# breakout.net
KiCad netlist of a schematic drawn in EAGLE
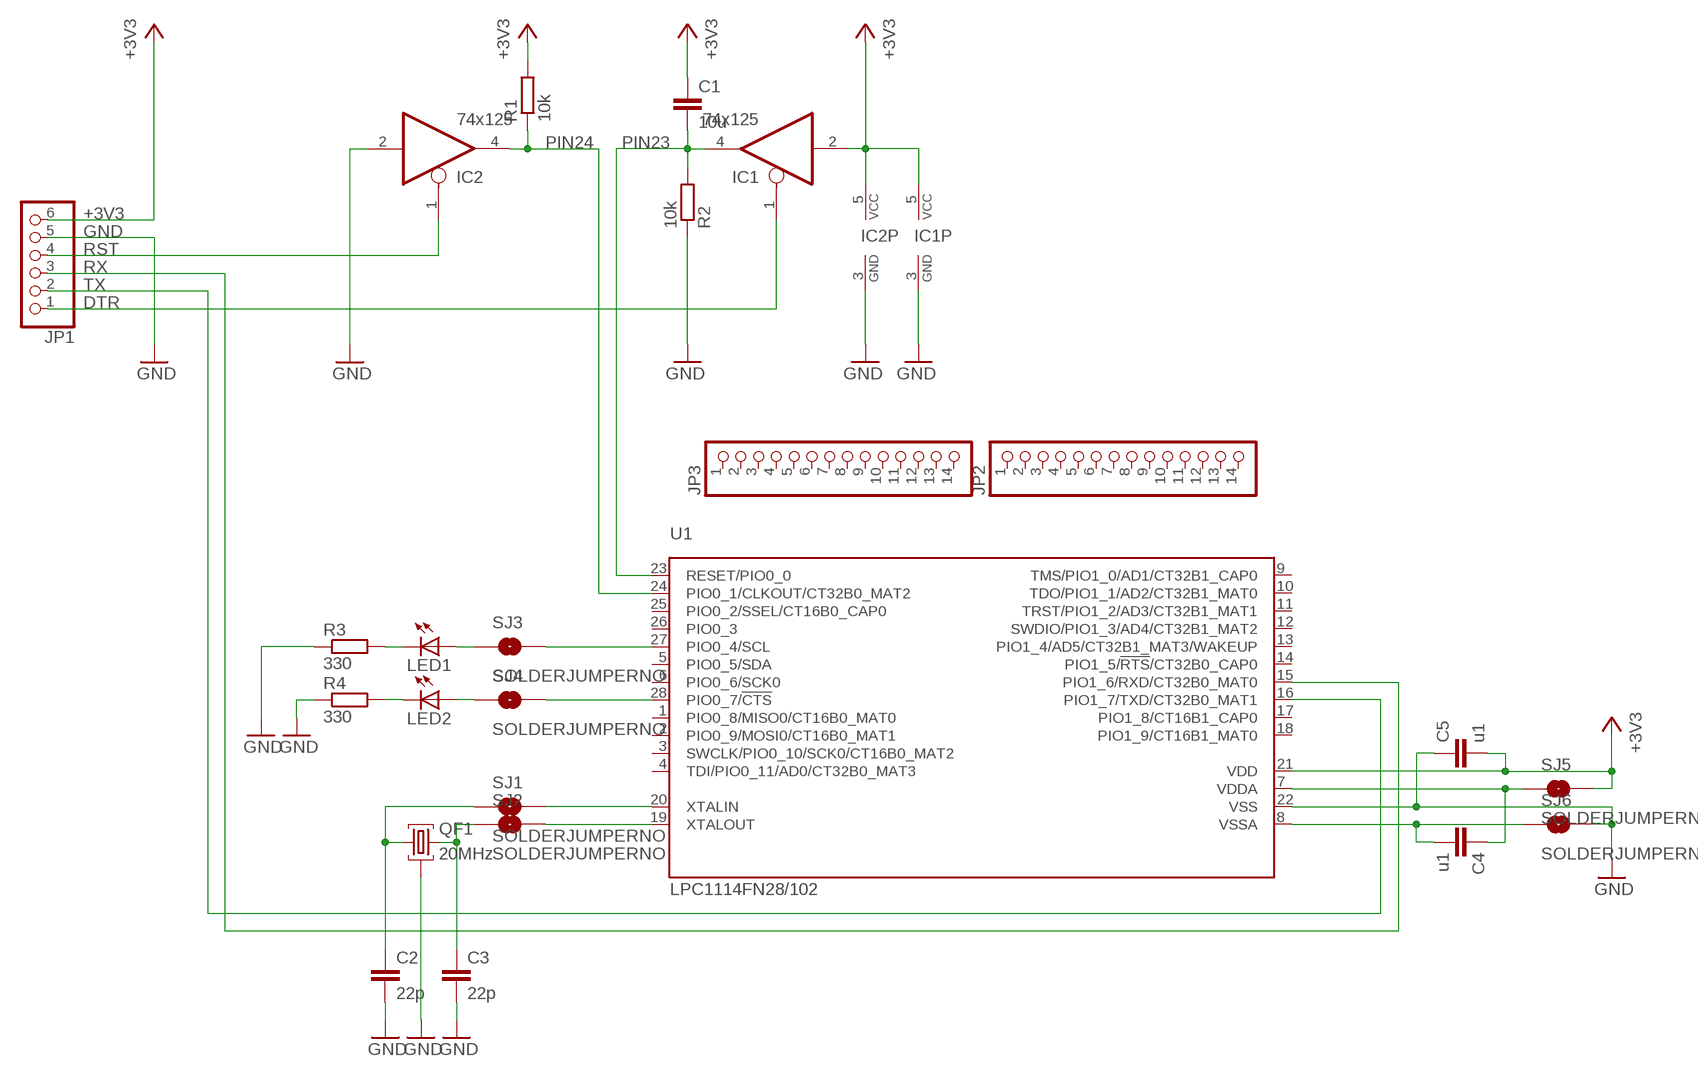
[diagram p0: schematic, sheet 1]

(export (version "E")
  (design (tool "Eeschema 10.0.6"))
  (components
    (comp (ref "C1")
      (value "10u")
      (footprint "eagle-import:C0805K")
      (libsource (lib "eagle-import") (part "C-EUC0805K"))
    )
    (comp (ref "C2")
      (value "22p")
      (footprint "eagle-import:C0805K")
      (libsource (lib "eagle-import") (part "C-EUC0805K"))
    )
    (comp (ref "C3")
      (value "22p")
      (footprint "eagle-import:C0805K")
      (libsource (lib "eagle-import") (part "C-EUC0805K"))
    )
    (comp (ref "C4")
      (value "u1")
      (footprint "eagle-import:C0805K")
      (libsource (lib "eagle-import") (part "C-EUC0805K"))
    )
    (comp (ref "C5")
      (value "u1")
      (footprint "eagle-import:C0805K")
      (libsource (lib "eagle-import") (part "C-EUC0805K"))
    )
    (comp (ref "IC1")
      (value "74x125")
      (footprint "eagle-import:SOT23-5")
      (libsource (lib "eagle-import") (part "741G125DBVAHC"))
    )
    (comp (ref "IC2")
      (value "74x125")
      (footprint "eagle-import:SOT23-5")
      (libsource (lib "eagle-import") (part "741G125DBVAHC"))
    )
    (comp (ref "JP1")
      (value "PINHD-1X6/90")
      (footprint "eagle-import:1X06_90")
      (libsource (lib "eagle-import") (part "PINHD-1X6/90"))
    )
    (comp (ref "JP2")
      (value "PINHD-1X14")
      (footprint "eagle-import:1X14")
      (libsource (lib "eagle-import") (part "PINHD-1X14"))
    )
    (comp (ref "JP3")
      (value "PINHD-1X14")
      (footprint "eagle-import:1X14")
      (libsource (lib "eagle-import") (part "PINHD-1X14"))
    )
    (comp (ref "LED1")
      (value "LEDLD260")
      (footprint "eagle-import:LD260")
      (libsource (lib "eagle-import") (part "LEDLD260"))
    )
    (comp (ref "LED2")
      (value "LEDLD260")
      (footprint "eagle-import:LD260")
      (libsource (lib "eagle-import") (part "LEDLD260"))
    )
    (comp (ref "QF1")
      (value "20MHz")
      (footprint "eagle-import:HC49U")
      (libsource (lib "eagle-import") (part "10MAHC49T7"))
    )
    (comp (ref "R1")
      (value "10k")
      (footprint "eagle-import:M0805")
      (libsource (lib "eagle-import") (part "R-EU_M0805"))
    )
    (comp (ref "R2")
      (value "10k")
      (footprint "eagle-import:M0805")
      (libsource (lib "eagle-import") (part "R-EU_M0805"))
    )
    (comp (ref "R3")
      (value "330")
      (footprint "eagle-import:M0805")
      (libsource (lib "eagle-import") (part "R-EU_M0805"))
    )
    (comp (ref "R4")
      (value "330")
      (footprint "eagle-import:M0805")
      (libsource (lib "eagle-import") (part "R-EU_M0805"))
    )
    (comp (ref "SJ1")
      (value "SOLDERJUMPERNO")
      (footprint "eagle-import:SJ_2S-NO")
      (libsource (lib "eagle-import") (part "SOLDERJUMPERNO"))
    )
    (comp (ref "SJ2")
      (value "SOLDERJUMPERNO")
      (footprint "eagle-import:SJ_2S-NO")
      (libsource (lib "eagle-import") (part "SOLDERJUMPERNO"))
    )
    (comp (ref "SJ3")
      (value "SOLDERJUMPERNO")
      (footprint "eagle-import:SJ_2S-NO")
      (libsource (lib "eagle-import") (part "SOLDERJUMPERNO"))
    )
    (comp (ref "SJ4")
      (value "SOLDERJUMPERNO")
      (footprint "eagle-import:SJ_2S-NO")
      (libsource (lib "eagle-import") (part "SOLDERJUMPERNO"))
    )
    (comp (ref "SJ5")
      (value "SOLDERJUMPERNO")
      (footprint "eagle-import:SJ_2S-NO")
      (libsource (lib "eagle-import") (part "SOLDERJUMPERNO"))
    )
    (comp (ref "SJ6")
      (value "SOLDERJUMPERNO")
      (footprint "eagle-import:SJ_2S-NO")
      (libsource (lib "eagle-import") (part "SOLDERJUMPERNO"))
    )
    (comp (ref "U1")
      (value "LPC1114FN28/102")
      (footprint "eagle-import:SOT117")
      (libsource (lib "eagle-import") (part "LPC1114FN28/102"))
    )
  )
  (nets
    (net (code "1") (name "+3V3") (class "Default")
      (node (ref "C1") (pin "1") (pinfunction "1_1") (pintype "passive"))
      (node (ref "C5") (pin "2") (pinfunction "2_2") (pintype "passive"))
      (node (ref "IC1") (pin "2") (pinfunction "I_2") (pintype "input"))
      (node (ref "IC1") (pin "5") (pinfunction "VCC_5") (pintype "power_in"))
      (node (ref "IC2") (pin "5") (pinfunction "VCC_5") (pintype "power_in"))
      (node (ref "JP1") (pin "6") (pinfunction "6_6") (pintype "passive"))
      (node (ref "R1") (pin "2") (pinfunction "2_2") (pintype "passive"))
      (node (ref "SJ5") (pin "2") (pinfunction "2_2") (pintype "passive"))
      (node (ref "U1") (pin "21") (pinfunction "VDD_21") (pintype "power_in"))
    )
    (net (code "2") (name "/DTR") (class "Default")
      (node (ref "IC1") (pin "1") (pinfunction "OE_1") (pintype "input"))
      (node (ref "JP1") (pin "1") (pinfunction "1_1") (pintype "passive"))
    )
    (net (code "3") (name "/PIN23") (class "Default")
      (node (ref "C1") (pin "2") (pinfunction "2_2") (pintype "passive"))
      (node (ref "IC1") (pin "4") (pinfunction "O_4") (pintype "tri_state"))
      (node (ref "R2") (pin "2") (pinfunction "2_2") (pintype "passive"))
      (node (ref "U1") (pin "23") (pinfunction "RESET/PIO0_0_23") (pintype "bidirectional"))
    )
    (net (code "4") (name "/PIN24") (class "Default")
      (node (ref "IC2") (pin "4") (pinfunction "O_4") (pintype "tri_state"))
      (node (ref "R1") (pin "1") (pinfunction "1_1") (pintype "passive"))
      (node (ref "U1") (pin "24") (pinfunction "PIO0_1/CLKOUT/CT32B0_MAT2_24") (pintype "bidirectional"))
    )
    (net (code "5") (name "/RST") (class "Default")
      (node (ref "IC2") (pin "1") (pinfunction "OE_1") (pintype "input"))
      (node (ref "JP1") (pin "4") (pinfunction "4_4") (pintype "passive"))
    )
    (net (code "6") (name "/RX") (class "Default")
      (node (ref "JP1") (pin "3") (pinfunction "3_3") (pintype "passive"))
      (node (ref "U1") (pin "15") (pinfunction "PIO1_6/RXD/CT32B0_MAT0_15") (pintype "bidirectional"))
    )
    (net (code "7") (name "/TX") (class "Default")
      (node (ref "JP1") (pin "2") (pinfunction "2_2") (pintype "passive"))
      (node (ref "U1") (pin "16") (pinfunction "PIO1_7/TXD/CT32B0_MAT1_16") (pintype "bidirectional"))
    )
    (net (code "8") (name "GND") (class "Default")
      (node (ref "C2") (pin "2") (pinfunction "2_2") (pintype "passive"))
      (node (ref "C3") (pin "2") (pinfunction "2_2") (pintype "passive"))
      (node (ref "C5") (pin "1") (pinfunction "1_1") (pintype "passive"))
      (node (ref "IC1") (pin "3") (pinfunction "GND_3") (pintype "power_in"))
      (node (ref "IC2") (pin "2") (pinfunction "I_2") (pintype "input"))
      (node (ref "IC2") (pin "3") (pinfunction "GND_3") (pintype "power_in"))
      (node (ref "JP1") (pin "5") (pinfunction "5_5") (pintype "passive"))
      (node (ref "QF1") (pin "2") (pinfunction "2_2") (pintype "passive"))
      (node (ref "R2") (pin "1") (pinfunction "1_1") (pintype "passive"))
      (node (ref "R3") (pin "1") (pinfunction "1_1") (pintype "passive"))
      (node (ref "R4") (pin "1") (pinfunction "1_1") (pintype "passive"))
      (node (ref "SJ6") (pin "2") (pinfunction "2_2") (pintype "passive"))
      (node (ref "U1") (pin "22") (pinfunction "VSS_22") (pintype "power_in"))
    )
    (net (code "9") (name "Net-(C2-Pad1)") (class "Default")
      (node (ref "C2") (pin "1") (pinfunction "1_1") (pintype "passive"))
      (node (ref "QF1") (pin "1") (pinfunction "1_1") (pintype "passive"))
      (node (ref "SJ1") (pin "1") (pinfunction "1_1") (pintype "passive"))
    )
    (net (code "10") (name "Net-(C3-Pad1)") (class "Default")
      (node (ref "C3") (pin "1") (pinfunction "1_1") (pintype "passive"))
      (node (ref "QF1") (pin "3") (pinfunction "3_3") (pintype "passive"))
      (node (ref "SJ2") (pin "1") (pinfunction "1_1") (pintype "passive"))
    )
    (net (code "11") (name "Net-(LED1-C)") (class "Default")
      (node (ref "LED1") (pin "K") (pinfunction "C_K") (pintype "passive"))
      (node (ref "R3") (pin "2") (pinfunction "2_2") (pintype "passive"))
    )
    (net (code "12") (name "Net-(LED1-PadA)") (class "Default")
      (node (ref "LED1") (pin "A") (pinfunction "A_A") (pintype "passive"))
      (node (ref "SJ3") (pin "1") (pinfunction "1_1") (pintype "passive"))
    )
    (net (code "13") (name "Net-(LED2-C)") (class "Default")
      (node (ref "LED2") (pin "K") (pinfunction "C_K") (pintype "passive"))
      (node (ref "R4") (pin "2") (pinfunction "2_2") (pintype "passive"))
    )
    (net (code "14") (name "Net-(LED2-PadA)") (class "Default")
      (node (ref "LED2") (pin "A") (pinfunction "A_A") (pintype "passive"))
      (node (ref "SJ4") (pin "1") (pinfunction "1_1") (pintype "passive"))
    )
    (net (code "15") (name "Net-(U1-PIO0_4{slash}SCL)") (class "Default")
      (node (ref "SJ3") (pin "2") (pinfunction "2_2") (pintype "passive"))
      (node (ref "U1") (pin "27") (pinfunction "PIO0_4/SCL_27") (pintype "bidirectional"))
    )
    (net (code "16") (name "Net-(U1-PIO0_7{slash}~{CTS})") (class "Default")
      (node (ref "SJ4") (pin "2") (pinfunction "2_2") (pintype "passive"))
      (node (ref "U1") (pin "28") (pinfunction "PIO0_7/~{CTS}_28") (pintype "bidirectional"))
    )
    (net (code "17") (name "Net-(U1-VDDA)") (class "Default")
      (node (ref "C4") (pin "1") (pinfunction "1_1") (pintype "passive"))
      (node (ref "SJ5") (pin "1") (pinfunction "1_1") (pintype "passive"))
      (node (ref "U1") (pin "7") (pinfunction "VDDA_7") (pintype "power_in"))
    )
    (net (code "18") (name "Net-(U1-VSSA)") (class "Default")
      (node (ref "C4") (pin "2") (pinfunction "2_2") (pintype "passive"))
      (node (ref "SJ6") (pin "1") (pinfunction "1_1") (pintype "passive"))
      (node (ref "U1") (pin "8") (pinfunction "VSSA_8") (pintype "power_in"))
    )
    (net (code "19") (name "Net-(U1-XTALIN)") (class "Default")
      (node (ref "SJ1") (pin "2") (pinfunction "2_2") (pintype "passive"))
      (node (ref "U1") (pin "20") (pinfunction "XTALIN_20") (pintype "input"))
    )
    (net (code "20") (name "Net-(U1-XTALOUT)") (class "Default")
      (node (ref "SJ2") (pin "2") (pinfunction "2_2") (pintype "passive"))
      (node (ref "U1") (pin "19") (pinfunction "XTALOUT_19") (pintype "output"))
    )
    (net (code "21") (name "unconnected-(JP2-Pad1)") (class "Default")
      (node (ref "JP2") (pin "1") (pinfunction "1_1") (pintype "passive"))
    )
    (net (code "22") (name "unconnected-(JP2-Pad2)") (class "Default")
      (node (ref "JP2") (pin "2") (pinfunction "2_2") (pintype "passive"))
    )
    (net (code "23") (name "unconnected-(JP2-Pad3)") (class "Default")
      (node (ref "JP2") (pin "3") (pinfunction "3_3") (pintype "passive"))
    )
    (net (code "24") (name "unconnected-(JP2-Pad4)") (class "Default")
      (node (ref "JP2") (pin "4") (pinfunction "4_4") (pintype "passive"))
    )
    (net (code "25") (name "unconnected-(JP2-Pad5)") (class "Default")
      (node (ref "JP2") (pin "5") (pinfunction "5_5") (pintype "passive"))
    )
    (net (code "26") (name "unconnected-(JP2-Pad6)") (class "Default")
      (node (ref "JP2") (pin "6") (pinfunction "6_6") (pintype "passive"))
    )
    (net (code "27") (name "unconnected-(JP2-Pad7)") (class "Default")
      (node (ref "JP2") (pin "7") (pinfunction "7_7") (pintype "passive"))
    )
    (net (code "28") (name "unconnected-(JP2-Pad8)") (class "Default")
      (node (ref "JP2") (pin "8") (pinfunction "8_8") (pintype "passive"))
    )
    (net (code "29") (name "unconnected-(JP2-Pad9)") (class "Default")
      (node (ref "JP2") (pin "9") (pinfunction "9_9") (pintype "passive"))
    )
    (net (code "30") (name "unconnected-(JP2-Pad10)") (class "Default")
      (node (ref "JP2") (pin "10") (pinfunction "10_10") (pintype "passive"))
    )
    (net (code "31") (name "unconnected-(JP2-Pad11)") (class "Default")
      (node (ref "JP2") (pin "11") (pinfunction "11_11") (pintype "passive"))
    )
    (net (code "32") (name "unconnected-(JP2-Pad12)") (class "Default")
      (node (ref "JP2") (pin "12") (pinfunction "12_12") (pintype "passive"))
    )
    (net (code "33") (name "unconnected-(JP2-Pad13)") (class "Default")
      (node (ref "JP2") (pin "13") (pinfunction "13_13") (pintype "passive"))
    )
    (net (code "34") (name "unconnected-(JP2-Pad14)") (class "Default")
      (node (ref "JP2") (pin "14") (pinfunction "14_14") (pintype "passive"))
    )
    (net (code "35") (name "unconnected-(JP3-Pad1)") (class "Default")
      (node (ref "JP3") (pin "1") (pinfunction "1_1") (pintype "passive"))
    )
    (net (code "36") (name "unconnected-(JP3-Pad2)") (class "Default")
      (node (ref "JP3") (pin "2") (pinfunction "2_2") (pintype "passive"))
    )
    (net (code "37") (name "unconnected-(JP3-Pad3)") (class "Default")
      (node (ref "JP3") (pin "3") (pinfunction "3_3") (pintype "passive"))
    )
    (net (code "38") (name "unconnected-(JP3-Pad4)") (class "Default")
      (node (ref "JP3") (pin "4") (pinfunction "4_4") (pintype "passive"))
    )
    (net (code "39") (name "unconnected-(JP3-Pad5)") (class "Default")
      (node (ref "JP3") (pin "5") (pinfunction "5_5") (pintype "passive"))
    )
    (net (code "40") (name "unconnected-(JP3-Pad6)") (class "Default")
      (node (ref "JP3") (pin "6") (pinfunction "6_6") (pintype "passive"))
    )
    (net (code "41") (name "unconnected-(JP3-Pad7)") (class "Default")
      (node (ref "JP3") (pin "7") (pinfunction "7_7") (pintype "passive"))
    )
    (net (code "42") (name "unconnected-(JP3-Pad8)") (class "Default")
      (node (ref "JP3") (pin "8") (pinfunction "8_8") (pintype "passive"))
    )
    (net (code "43") (name "unconnected-(JP3-Pad9)") (class "Default")
      (node (ref "JP3") (pin "9") (pinfunction "9_9") (pintype "passive"))
    )
    (net (code "44") (name "unconnected-(JP3-Pad10)") (class "Default")
      (node (ref "JP3") (pin "10") (pinfunction "10_10") (pintype "passive"))
    )
    (net (code "45") (name "unconnected-(JP3-Pad11)") (class "Default")
      (node (ref "JP3") (pin "11") (pinfunction "11_11") (pintype "passive"))
    )
    (net (code "46") (name "unconnected-(JP3-Pad12)") (class "Default")
      (node (ref "JP3") (pin "12") (pinfunction "12_12") (pintype "passive"))
    )
    (net (code "47") (name "unconnected-(JP3-Pad13)") (class "Default")
      (node (ref "JP3") (pin "13") (pinfunction "13_13") (pintype "passive"))
    )
    (net (code "48") (name "unconnected-(JP3-Pad14)") (class "Default")
      (node (ref "JP3") (pin "14") (pinfunction "14_14") (pintype "passive"))
    )
    (net (code "49") (name "unconnected-(U1-PIO0_2{slash}SSEL{slash}CT16B0_CAP0-Pad25)") (class "Default")
      (node (ref "U1") (pin "25") (pinfunction "PIO0_2/SSEL/CT16B0_CAP0_25") (pintype "bidirectional"))
    )
    (net (code "50") (name "unconnected-(U1-PIO0_3-Pad26)") (class "Default")
      (node (ref "U1") (pin "26") (pinfunction "PIO0_3_26") (pintype "bidirectional"))
    )
    (net (code "51") (name "unconnected-(U1-PIO0_5{slash}SDA-Pad5)") (class "Default")
      (node (ref "U1") (pin "5") (pinfunction "PIO0_5/SDA_5") (pintype "bidirectional"))
    )
    (net (code "52") (name "unconnected-(U1-PIO0_6{slash}SCK0-Pad6)") (class "Default")
      (node (ref "U1") (pin "6") (pinfunction "PIO0_6/SCK0_6") (pintype "bidirectional"))
    )
    (net (code "53") (name "unconnected-(U1-PIO0_8{slash}MISO0{slash}CT16B0_MAT0-Pad1)") (class "Default")
      (node (ref "U1") (pin "1") (pinfunction "PIO0_8/MISO0/CT16B0_MAT0_1") (pintype "bidirectional"))
    )
    (net (code "54") (name "unconnected-(U1-PIO0_9{slash}MOSI0{slash}CT16B0_MAT1-Pad2)") (class "Default")
      (node (ref "U1") (pin "2") (pinfunction "PIO0_9/MOSI0/CT16B0_MAT1_2") (pintype "bidirectional"))
    )
    (net (code "55") (name "unconnected-(U1-PIO1_4{slash}AD5{slash}CT32B1_MAT3{slash}WAKEUP-Pad13)") (class "Default")
      (node (ref "U1") (pin "13") (pinfunction "PIO1_4/AD5/CT32B1_MAT3/WAKEUP_13") (pintype "bidirectional"))
    )
    (net (code "56") (name "unconnected-(U1-PIO1_5{slash}~{RTS}{slash}CT32B0_CAP0-Pad14)") (class "Default")
      (node (ref "U1") (pin "14") (pinfunction "PIO1_5/~{RTS}/CT32B0_CAP0_14") (pintype "bidirectional"))
    )
    (net (code "57") (name "unconnected-(U1-PIO1_8{slash}CT16B1_CAP0-Pad17)") (class "Default")
      (node (ref "U1") (pin "17") (pinfunction "PIO1_8/CT16B1_CAP0_17") (pintype "bidirectional"))
    )
    (net (code "58") (name "unconnected-(U1-PIO1_9{slash}CT16B1_MAT0-Pad18)") (class "Default")
      (node (ref "U1") (pin "18") (pinfunction "PIO1_9/CT16B1_MAT0_18") (pintype "bidirectional"))
    )
    (net (code "59") (name "unconnected-(U1-SWCLK{slash}PIO0_10{slash}SCK0{slash}CT16B0_MAT2-Pad3)") (class "Default")
      (node (ref "U1") (pin "3") (pinfunction "SWCLK/PIO0_10/SCK0/CT16B0_MAT2_3") (pintype "bidirectional"))
    )
    (net (code "60") (name "unconnected-(U1-SWDIO{slash}PIO1_3{slash}AD4{slash}CT32B1_MAT2-Pad12)") (class "Default")
      (node (ref "U1") (pin "12") (pinfunction "SWDIO/PIO1_3/AD4/CT32B1_MAT2_12") (pintype "bidirectional"))
    )
    (net (code "61") (name "unconnected-(U1-TDI{slash}PIO0_11{slash}AD0{slash}CT32B0_MAT3-Pad4)") (class "Default")
      (node (ref "U1") (pin "4") (pinfunction "TDI/PIO0_11/AD0/CT32B0_MAT3_4") (pintype "bidirectional"))
    )
    (net (code "62") (name "unconnected-(U1-TDO{slash}PIO1_1{slash}AD2{slash}CT32B1_MAT0-Pad10)") (class "Default")
      (node (ref "U1") (pin "10") (pinfunction "TDO/PIO1_1/AD2/CT32B1_MAT0_10") (pintype "bidirectional"))
    )
    (net (code "63") (name "unconnected-(U1-TMS{slash}PIO1_0{slash}AD1{slash}CT32B1_CAP0-Pad9)") (class "Default")
      (node (ref "U1") (pin "9") (pinfunction "TMS/PIO1_0/AD1/CT32B1_CAP0_9") (pintype "bidirectional"))
    )
    (net (code "64") (name "unconnected-(U1-TRST{slash}PIO1_2{slash}AD3{slash}CT32B1_MAT1-Pad11)") (class "Default")
      (node (ref "U1") (pin "11") (pinfunction "TRST/PIO1_2/AD3/CT32B1_MAT1_11") (pintype "bidirectional"))
    )
  )
)
